# EuroESP32.net
KiCad netlist of a schematic drawn in EAGLE
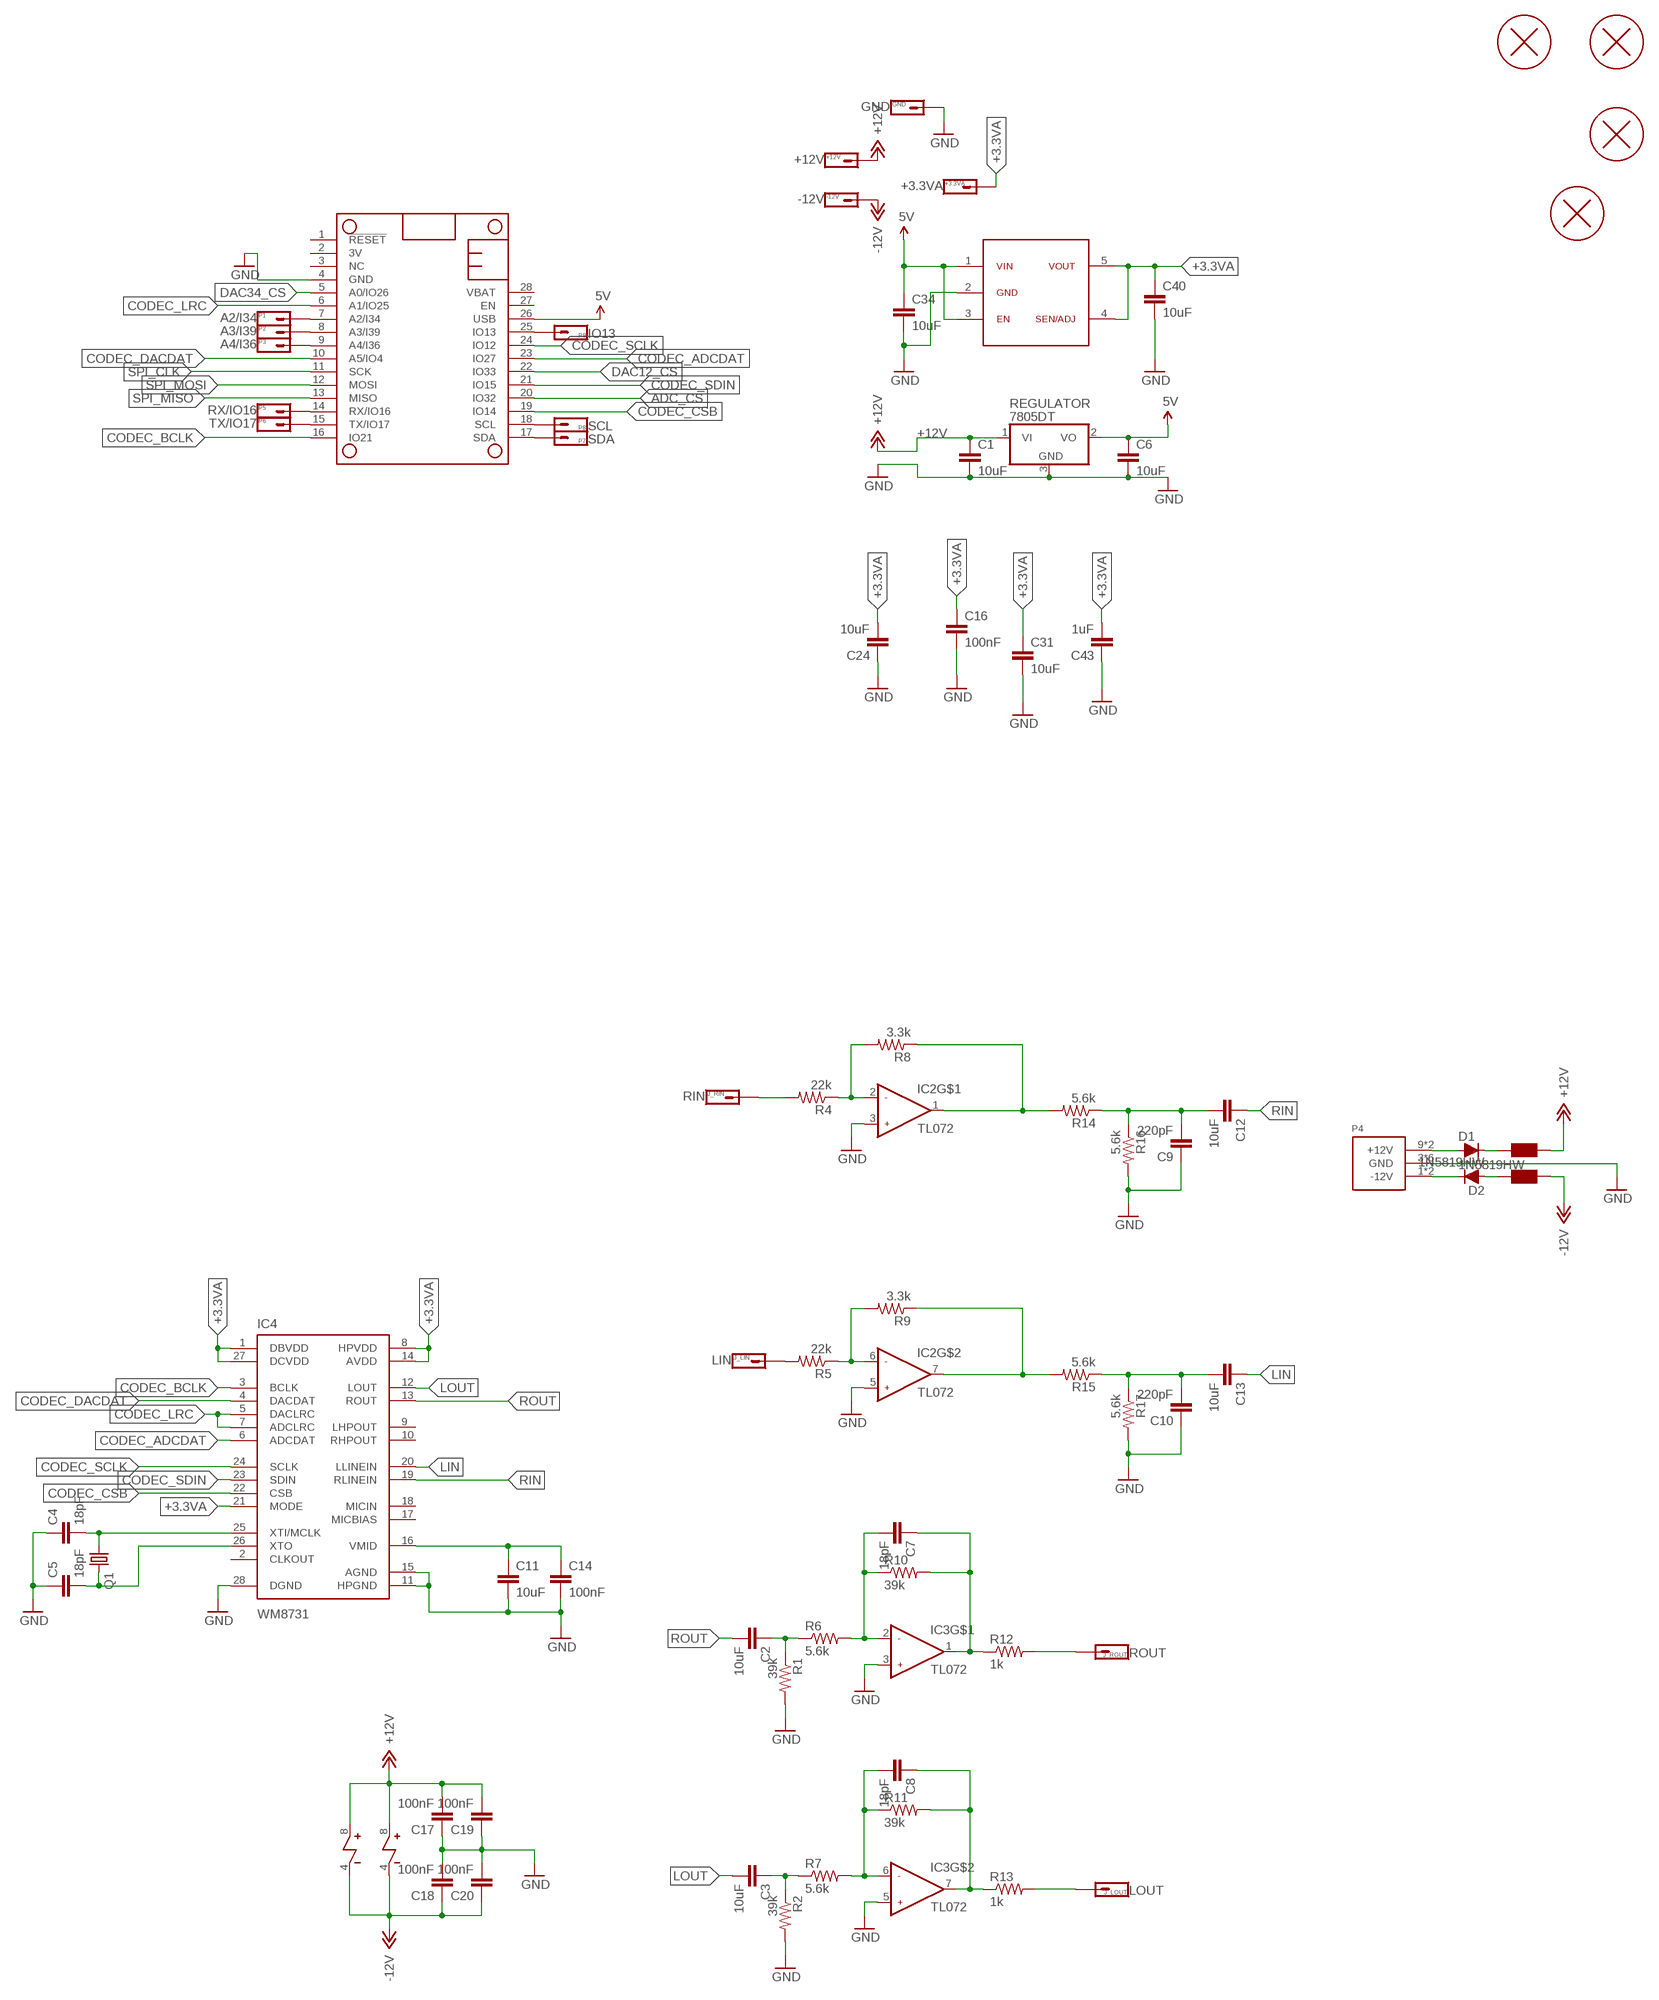
[diagram p0: schematic, sheet 1, part 1 of 2]
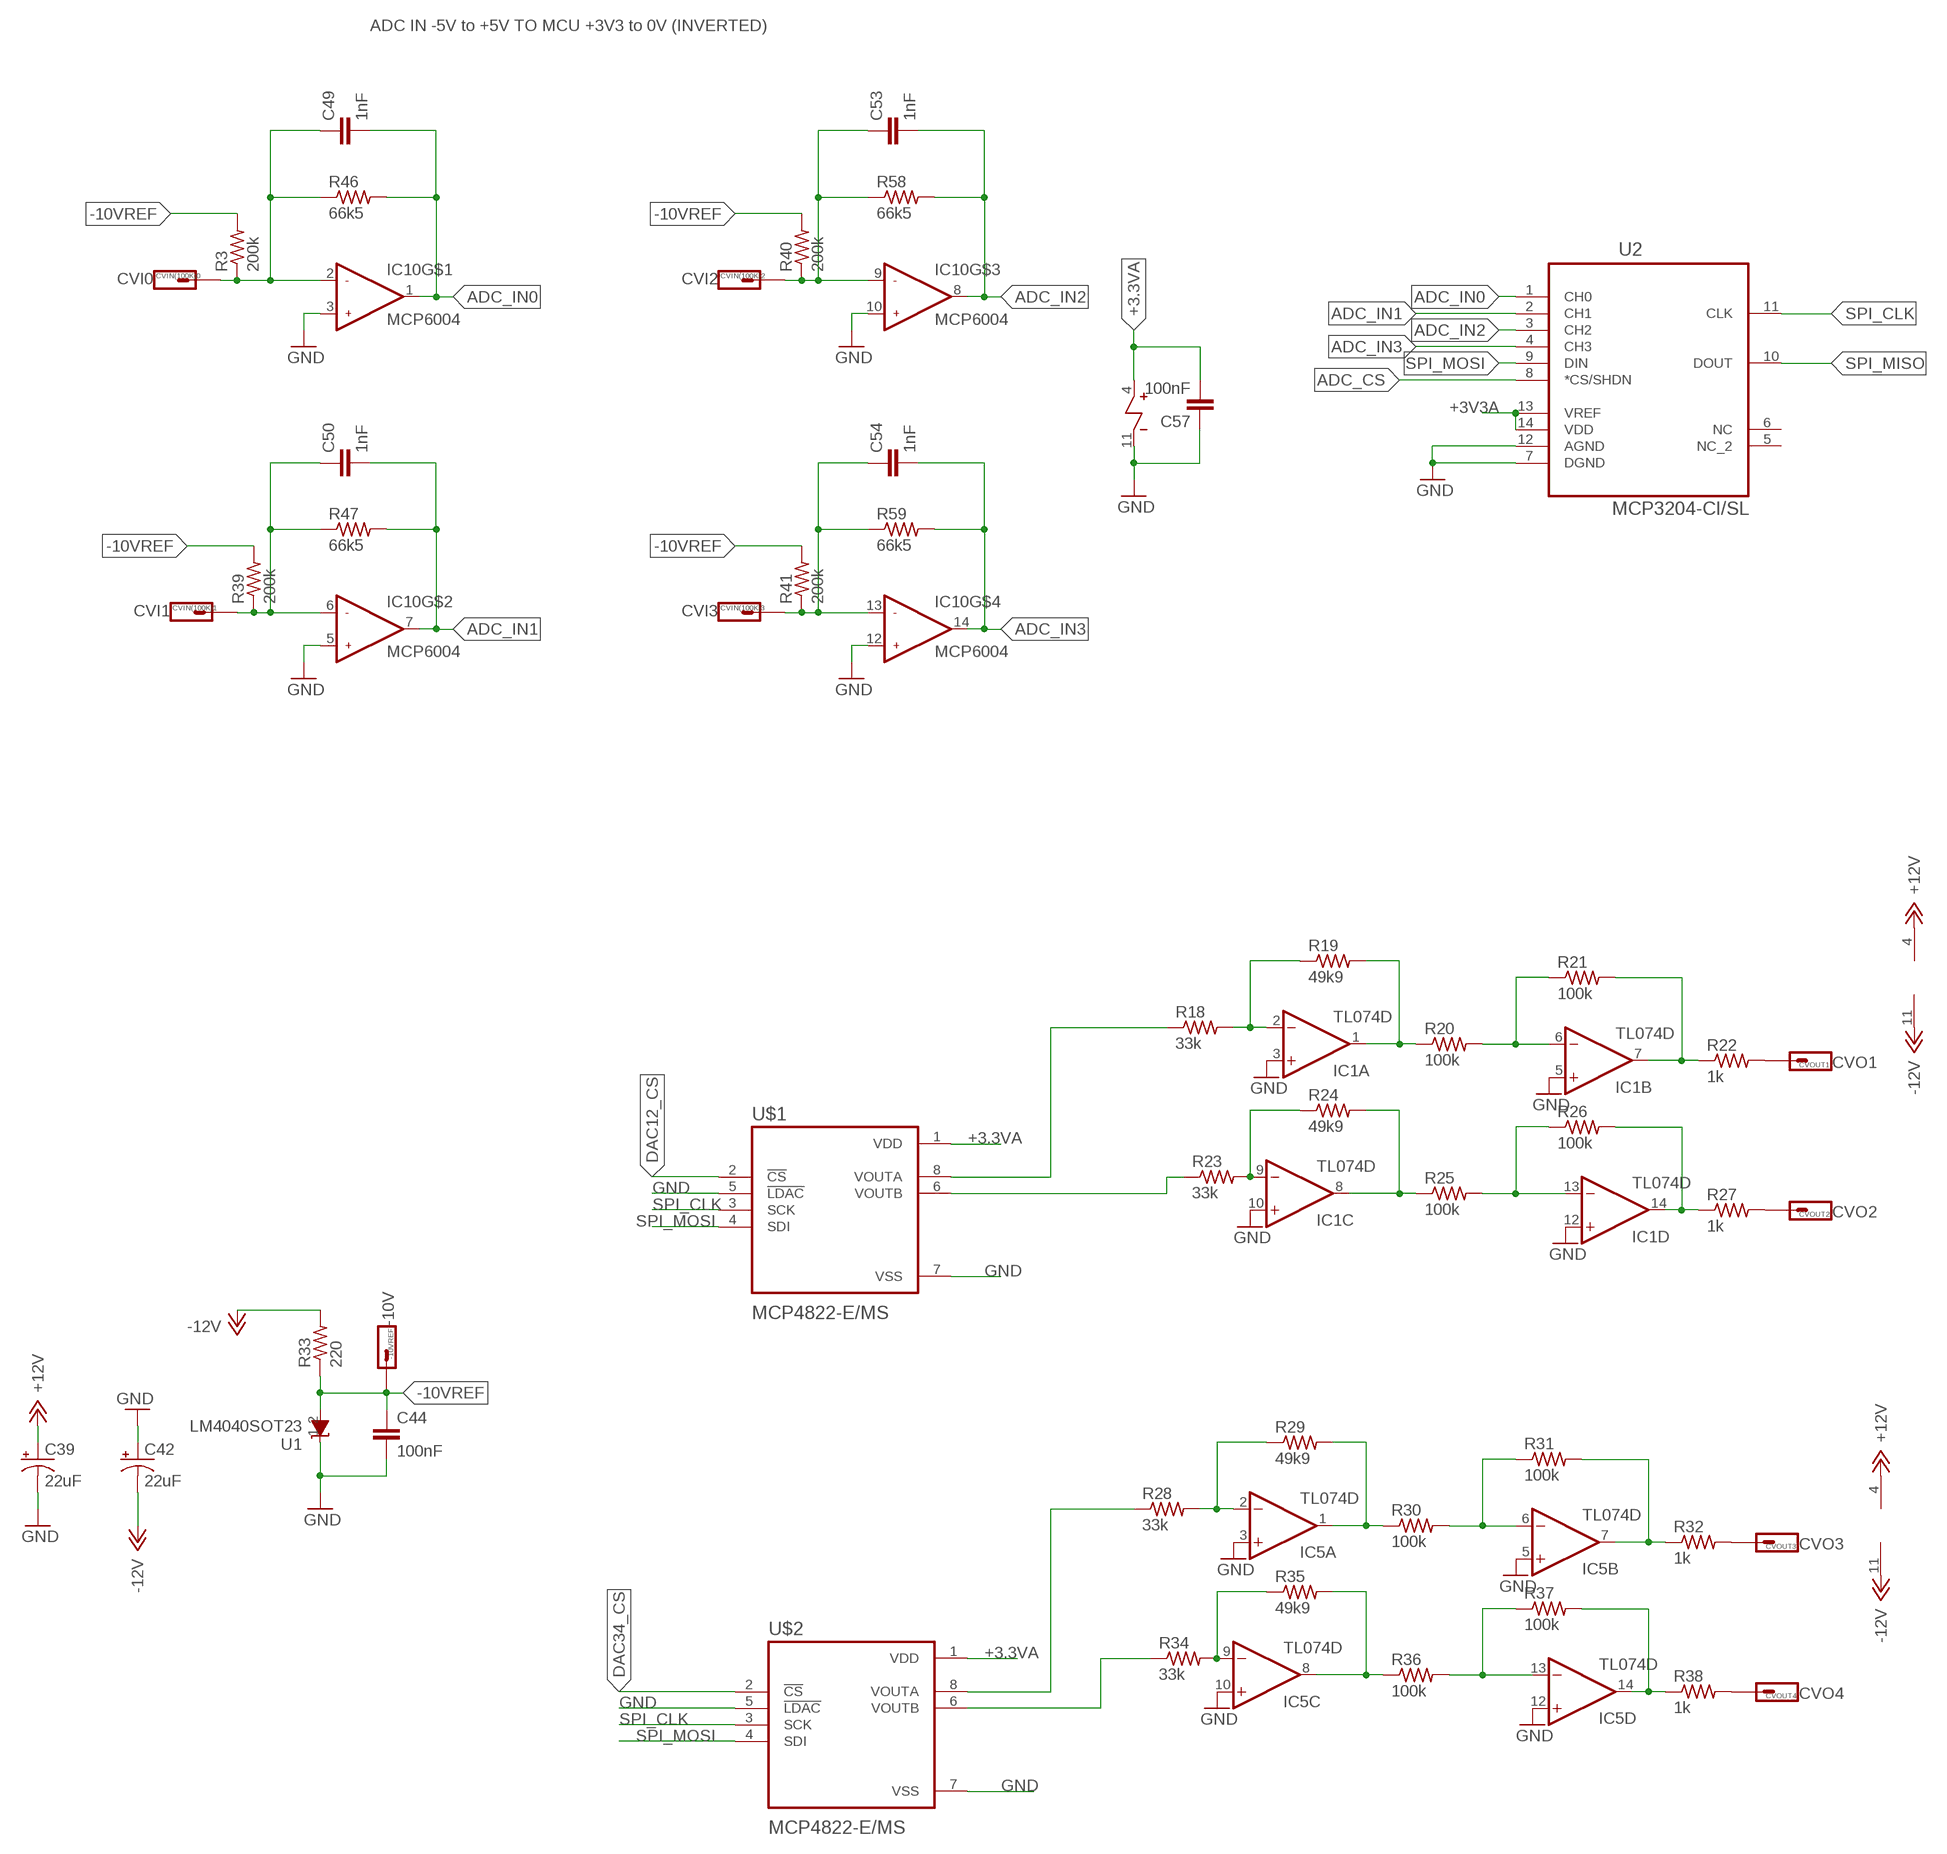
[diagram p1: schematic, sheet 1, part 2 of 2]

(export (version "E")
  (design (tool "Eeschema 10.0.6"))
  (components
    (comp (ref "+3.3VA")
      (value "+3.3VA")
      (footprint "eagle-import:1X01_SIDE_NAME")
      (libsource (lib "eagle-import") (part "HEADER-1X1"))
    )
    (comp (ref "+12V")
      (value "+12V")
      (footprint "eagle-import:1X01_SIDE_NAME")
      (libsource (lib "eagle-import") (part "HEADER-1X1"))
    )
    (comp (ref "-10VREF")
      (value "-10V")
      (footprint "eagle-import:1X01_SIDE_NAME")
      (libsource (lib "eagle-import") (part "HEADER-1X1"))
    )
    (comp (ref "-12V")
      (value "-12V")
      (footprint "eagle-import:1X01_SIDE_NAME")
      (libsource (lib "eagle-import") (part "HEADER-1X1"))
    )
    (comp (ref "C1")
      (value "10uF")
      (footprint "eagle-import:R1210")
      (libsource (lib "eagle-import") (part "CAPACITOR1210"))
    )
    (comp (ref "C2")
      (value "10uF")
      (footprint "eagle-import:R0805")
      (libsource (lib "eagle-import") (part "CAPACITOR0805"))
    )
    (comp (ref "C3")
      (value "10uF")
      (footprint "eagle-import:R0805")
      (libsource (lib "eagle-import") (part "CAPACITOR0805"))
    )
    (comp (ref "C4")
      (value "18pF")
      (footprint "eagle-import:RESISTOR_0603")
      (libsource (lib "eagle-import") (part "CAPACITOR"))
    )
    (comp (ref "C5")
      (value "18pF")
      (footprint "eagle-import:RESISTOR_0603")
      (libsource (lib "eagle-import") (part "CAPACITOR"))
    )
    (comp (ref "C6")
      (value "10uF")
      (footprint "eagle-import:R1210")
      (libsource (lib "eagle-import") (part "CAPACITOR1210"))
    )
    (comp (ref "C7")
      (value "18pF")
      (footprint "eagle-import:RESISTOR_0603")
      (libsource (lib "eagle-import") (part "CAPACITOR"))
    )
    (comp (ref "C8")
      (value "18pF")
      (footprint "eagle-import:RESISTOR_0603")
      (libsource (lib "eagle-import") (part "CAPACITOR"))
    )
    (comp (ref "C9")
      (value "220pF")
      (footprint "eagle-import:RESISTOR_0603")
      (libsource (lib "eagle-import") (part "CAPACITOR"))
    )
    (comp (ref "C10")
      (value "220pF")
      (footprint "eagle-import:RESISTOR_0603")
      (libsource (lib "eagle-import") (part "CAPACITOR"))
    )
    (comp (ref "C11")
      (value "10uF")
      (footprint "eagle-import:R0805")
      (libsource (lib "eagle-import") (part "CAPACITOR0805"))
    )
    (comp (ref "C12")
      (value "10uF")
      (footprint "eagle-import:R0805")
      (libsource (lib "eagle-import") (part "CAPACITOR0805"))
    )
    (comp (ref "C13")
      (value "10uF")
      (footprint "eagle-import:R0805")
      (libsource (lib "eagle-import") (part "CAPACITOR0805"))
    )
    (comp (ref "C14")
      (value "100nF")
      (footprint "eagle-import:RESISTOR_0603")
      (libsource (lib "eagle-import") (part "CAPACITOR"))
    )
    (comp (ref "C16")
      (value "100nF")
      (footprint "eagle-import:RESISTOR_0603")
      (libsource (lib "eagle-import") (part "CAPACITOR"))
    )
    (comp (ref "C17")
      (value "100nF")
      (footprint "eagle-import:RESISTOR_0603")
      (libsource (lib "eagle-import") (part "CAPACITOR"))
    )
    (comp (ref "C18")
      (value "100nF")
      (footprint "eagle-import:RESISTOR_0603")
      (libsource (lib "eagle-import") (part "CAPACITOR"))
    )
    (comp (ref "C19")
      (value "100nF")
      (footprint "eagle-import:RESISTOR_0603")
      (libsource (lib "eagle-import") (part "CAPACITOR"))
    )
    (comp (ref "C20")
      (value "100nF")
      (footprint "eagle-import:RESISTOR_0603")
      (libsource (lib "eagle-import") (part "CAPACITOR"))
    )
    (comp (ref "C24")
      (value "10uF")
      (footprint "eagle-import:R0805")
      (libsource (lib "eagle-import") (part "CAPACITOR0805"))
    )
    (comp (ref "C31")
      (value "10uF")
      (footprint "eagle-import:R0805")
      (libsource (lib "eagle-import") (part "CAPACITOR0805"))
    )
    (comp (ref "C34")
      (value "10uF")
      (footprint "eagle-import:R1210")
      (libsource (lib "eagle-import") (part "CAPACITOR1210"))
    )
    (comp (ref "C39")
      (value "22uF")
      (footprint "eagle-import:1206_POL")
      (libsource (lib "eagle-import") (part "CAP_POL1206_TANT"))
    )
    (comp (ref "C40")
      (value "10uF")
      (footprint "eagle-import:R0805")
      (libsource (lib "eagle-import") (part "CAPACITOR0805"))
    )
    (comp (ref "C42")
      (value "22uF")
      (footprint "eagle-import:1206_POL")
      (libsource (lib "eagle-import") (part "CAP_POL1206_TANT"))
    )
    (comp (ref "C43")
      (value "1uF")
      (footprint "eagle-import:RESISTOR_0603")
      (libsource (lib "eagle-import") (part "CAPACITOR"))
    )
    (comp (ref "C44")
      (value "100nF")
      (footprint "eagle-import:RESISTOR_0603")
      (libsource (lib "eagle-import") (part "CAPACITOR"))
    )
    (comp (ref "C49")
      (value "1nF")
      (footprint "eagle-import:RESISTOR_0603")
      (libsource (lib "eagle-import") (part "CAPACITOR"))
    )
    (comp (ref "C50")
      (value "1nF")
      (footprint "eagle-import:RESISTOR_0603")
      (libsource (lib "eagle-import") (part "CAPACITOR"))
    )
    (comp (ref "C53")
      (value "1nF")
      (footprint "eagle-import:RESISTOR_0603")
      (libsource (lib "eagle-import") (part "CAPACITOR"))
    )
    (comp (ref "C54")
      (value "1nF")
      (footprint "eagle-import:RESISTOR_0603")
      (libsource (lib "eagle-import") (part "CAPACITOR"))
    )
    (comp (ref "C57")
      (value "100nF")
      (footprint "eagle-import:RESISTOR_0603")
      (libsource (lib "eagle-import") (part "CAPACITOR"))
    )
    (comp (ref "CVIN(100K)0")
      (value "CVI0")
      (footprint "eagle-import:1X01_SIDE_NAME")
      (libsource (lib "eagle-import") (part "HEADER-1X1"))
    )
    (comp (ref "CVIN(100K)1")
      (value "CVI1")
      (footprint "eagle-import:1X01_SIDE_NAME")
      (libsource (lib "eagle-import") (part "HEADER-1X1"))
    )
    (comp (ref "CVIN(100K)2")
      (value "CVI2")
      (footprint "eagle-import:1X01_SIDE_NAME")
      (libsource (lib "eagle-import") (part "HEADER-1X1"))
    )
    (comp (ref "CVIN(100K)3")
      (value "CVI3")
      (footprint "eagle-import:1X01_SIDE_NAME")
      (libsource (lib "eagle-import") (part "HEADER-1X1"))
    )
    (comp (ref "CVOUT1")
      (value "CVO1")
      (footprint "eagle-import:1X01_SIDE_NAME")
      (libsource (lib "eagle-import") (part "HEADER-1X1"))
    )
    (comp (ref "CVOUT2")
      (value "CVO2")
      (footprint "eagle-import:1X01_SIDE_NAME")
      (libsource (lib "eagle-import") (part "HEADER-1X1"))
    )
    (comp (ref "CVOUT3")
      (value "CVO3")
      (footprint "eagle-import:1X01_SIDE_NAME")
      (libsource (lib "eagle-import") (part "HEADER-1X1"))
    )
    (comp (ref "CVOUT4")
      (value "CVO4")
      (footprint "eagle-import:1X01_SIDE_NAME")
      (libsource (lib "eagle-import") (part "HEADER-1X1"))
    )
    (comp (ref "D1")
      (value "1N5819HW")
      (footprint "eagle-import:SOD123")
      (libsource (lib "eagle-import") (part "DIODE"))
    )
    (comp (ref "D2")
      (value "1N5819HW")
      (footprint "eagle-import:SOD123")
      (libsource (lib "eagle-import") (part "DIODE"))
    )
    (comp (ref "F1")
      (value "Würth Electronics 742792664")
      (footprint "eagle-import:R0805")
      (libsource (lib "eagle-import") (part "FERRITE-BEAD0805"))
    )
    (comp (ref "F2")
      (value "Würth Electronics 742792664")
      (footprint "eagle-import:R0805")
      (libsource (lib "eagle-import") (part "FERRITE-BEAD0805"))
    )
    (comp (ref "GND")
      (value "GND")
      (footprint "eagle-import:1X01_SIDE_NAME")
      (libsource (lib "eagle-import") (part "HEADER-1X1"))
    )
    (comp (ref "H1")
      (value "PCB_SCREW")
      (footprint "eagle-import:PCB_SCREW")
      (libsource (lib "eagle-import") (part "PCB_SCREW"))
    )
    (comp (ref "H3")
      (value "PCB_SCREW")
      (footprint "eagle-import:PCB_SCREW")
      (libsource (lib "eagle-import") (part "PCB_SCREW"))
    )
    (comp (ref "H4")
      (value "PCB_SCREW")
      (footprint "eagle-import:PCB_SCREW")
      (libsource (lib "eagle-import") (part "PCB_SCREW"))
    )
    (comp (ref "H5")
      (value "PCB_SCREW")
      (footprint "eagle-import:PCB_SCREW")
      (libsource (lib "eagle-import") (part "PCB_SCREW"))
    )
    (comp (ref "IC1")
      (value "TL074D")
      (footprint "eagle-import:SO14")
      (libsource (lib "eagle-import") (part "TL074D"))
    )
    (comp (ref "IC2")
      (value "TL072")
      (footprint "eagle-import:SOIC8")
      (libsource (lib "eagle-import") (part "OPAMP_DUAL"))
    )
    (comp (ref "IC3")
      (value "TL072")
      (footprint "eagle-import:SOIC8")
      (libsource (lib "eagle-import") (part "OPAMP_DUAL"))
    )
    (comp (ref "IC4")
      (value "WM8731")
      (footprint "eagle-import:SSOP28")
      (libsource (lib "eagle-import") (part "WM8731"))
    )
    (comp (ref "IC5")
      (value "TL074D")
      (footprint "eagle-import:SO14")
      (libsource (lib "eagle-import") (part "TL074D"))
    )
    (comp (ref "IC7")
      (value "ADP7118")
      (footprint "eagle-import:SOT23-5L")
      (libsource (lib "eagle-import") (part "ADP7118"))
    )
    (comp (ref "IC10")
      (value "MCP6004")
      (footprint "eagle-import:TSSOP14")
      (libsource (lib "eagle-import") (part "OPAMP_QUADPWR"))
    )
    (comp (ref "J_LIN")
      (value "LIN")
      (footprint "eagle-import:1X01_SIDE_NAME")
      (libsource (lib "eagle-import") (part "HEADER-1X1"))
    )
    (comp (ref "J_LOUT")
      (value "LOUT")
      (footprint "eagle-import:1X01_SIDE_NAME")
      (libsource (lib "eagle-import") (part "HEADER-1X1"))
    )
    (comp (ref "J_RIN")
      (value "RIN")
      (footprint "eagle-import:1X01_SIDE_NAME")
      (libsource (lib "eagle-import") (part "HEADER-1X1"))
    )
    (comp (ref "J_ROUT")
      (value "ROUT")
      (footprint "eagle-import:1X01_SIDE_NAME")
      (libsource (lib "eagle-import") (part "HEADER-1X1"))
    )
    (comp (ref "MS2")
      (value "FEATHER_HUZZAH32NO_DRILL")
      (footprint "eagle-import:FEATHERWING_NODRILL")
      (libsource (lib "eagle-import") (part "FEATHER_HUZZAH32NO_DRILL"))
    )
    (comp (ref "P1")
      (value "A2/I34")
      (footprint "eagle-import:1X01_SIDE_NAME")
      (libsource (lib "eagle-import") (part "HEADER-1X1"))
    )
    (comp (ref "P2")
      (value "A3/I39")
      (footprint "eagle-import:1X01_SIDE_NAME")
      (libsource (lib "eagle-import") (part "HEADER-1X1"))
    )
    (comp (ref "P3")
      (value "A4/I36")
      (footprint "eagle-import:1X01_SIDE_NAME")
      (libsource (lib "eagle-import") (part "HEADER-1X1"))
    )
    (comp (ref "P4")
      (value "POWER_SIMPLE10")
      (footprint "eagle-import:POWER_10")
      (libsource (lib "eagle-import") (part "POWER_SIMPLE10"))
    )
    (comp (ref "P5")
      (value "RX/IO16")
      (footprint "eagle-import:1X01_SIDE_NAME")
      (libsource (lib "eagle-import") (part "HEADER-1X1"))
    )
    (comp (ref "P6")
      (value "TX/IO17")
      (footprint "eagle-import:1X01_SIDE_NAME")
      (libsource (lib "eagle-import") (part "HEADER-1X1"))
    )
    (comp (ref "P7")
      (value "SDA")
      (footprint "eagle-import:1X01_SIDE_NAME")
      (libsource (lib "eagle-import") (part "HEADER-1X1"))
    )
    (comp (ref "P8")
      (value "SCL")
      (footprint "eagle-import:1X01_SIDE_NAME")
      (libsource (lib "eagle-import") (part "HEADER-1X1"))
    )
    (comp (ref "P9")
      (value "IO13")
      (footprint "eagle-import:1X01_SIDE_NAME")
      (libsource (lib "eagle-import") (part "HEADER-1X1"))
    )
    (comp (ref "Q1")
      (value "CRYSTAL")
      (footprint "eagle-import:HC49UP")
      (libsource (lib "eagle-import") (part "CRYSTAL"))
    )
    (comp (ref "R1")
      (value "39k")
      (footprint "eagle-import:RESISTOR_0603")
      (libsource (lib "eagle-import") (part "RESISTOR"))
    )
    (comp (ref "R2")
      (value "39k")
      (footprint "eagle-import:RESISTOR_0603")
      (libsource (lib "eagle-import") (part "RESISTOR"))
    )
    (comp (ref "R3")
      (value "200k")
      (footprint "eagle-import:RESISTOR_0603")
      (libsource (lib "eagle-import") (part "RESISTOR"))
    )
    (comp (ref "R4")
      (value "22k")
      (footprint "eagle-import:RESISTOR_0603")
      (libsource (lib "eagle-import") (part "RESISTOR"))
    )
    (comp (ref "R5")
      (value "22k")
      (footprint "eagle-import:RESISTOR_0603")
      (libsource (lib "eagle-import") (part "RESISTOR"))
    )
    (comp (ref "R6")
      (value "5.6k")
      (footprint "eagle-import:RESISTOR_0603")
      (libsource (lib "eagle-import") (part "RESISTOR"))
    )
    (comp (ref "R7")
      (value "5.6k")
      (footprint "eagle-import:RESISTOR_0603")
      (libsource (lib "eagle-import") (part "RESISTOR"))
    )
    (comp (ref "R8")
      (value "3.3k")
      (footprint "eagle-import:RESISTOR_0603")
      (libsource (lib "eagle-import") (part "RESISTOR"))
    )
    (comp (ref "R9")
      (value "3.3k")
      (footprint "eagle-import:RESISTOR_0603")
      (libsource (lib "eagle-import") (part "RESISTOR"))
    )
    (comp (ref "R10")
      (value "39k")
      (footprint "eagle-import:RESISTOR_0603")
      (libsource (lib "eagle-import") (part "RESISTOR"))
    )
    (comp (ref "R11")
      (value "39k")
      (footprint "eagle-import:RESISTOR_0603")
      (libsource (lib "eagle-import") (part "RESISTOR"))
    )
    (comp (ref "R12")
      (value "1k")
      (footprint "eagle-import:RESISTOR_0603")
      (libsource (lib "eagle-import") (part "RESISTOR"))
    )
    (comp (ref "R13")
      (value "1k")
      (footprint "eagle-import:RESISTOR_0603")
      (libsource (lib "eagle-import") (part "RESISTOR"))
    )
    (comp (ref "R14")
      (value "5.6k")
      (footprint "eagle-import:RESISTOR_0603")
      (libsource (lib "eagle-import") (part "RESISTOR"))
    )
    (comp (ref "R15")
      (value "5.6k")
      (footprint "eagle-import:RESISTOR_0603")
      (libsource (lib "eagle-import") (part "RESISTOR"))
    )
    (comp (ref "R16")
      (value "5.6k")
      (footprint "eagle-import:RESISTOR_0603")
      (libsource (lib "eagle-import") (part "RESISTOR"))
    )
    (comp (ref "R17")
      (value "5.6k")
      (footprint "eagle-import:RESISTOR_0603")
      (libsource (lib "eagle-import") (part "RESISTOR"))
    )
    (comp (ref "R18")
      (value "33k")
      (footprint "eagle-import:RESISTOR_0603")
      (libsource (lib "eagle-import") (part "RESISTOR"))
    )
    (comp (ref "R19")
      (value "49k9")
      (footprint "eagle-import:RESISTOR_0603")
      (libsource (lib "eagle-import") (part "RESISTOR"))
    )
    (comp (ref "R20")
      (value "100k")
      (footprint "eagle-import:RESISTOR_0603")
      (libsource (lib "eagle-import") (part "RESISTOR"))
    )
    (comp (ref "R21")
      (value "100k")
      (footprint "eagle-import:RESISTOR_0603")
      (libsource (lib "eagle-import") (part "RESISTOR"))
    )
    (comp (ref "R22")
      (value "1k")
      (footprint "eagle-import:RESISTOR_0603")
      (libsource (lib "eagle-import") (part "RESISTOR"))
    )
    (comp (ref "R23")
      (value "33k")
      (footprint "eagle-import:RESISTOR_0603")
      (libsource (lib "eagle-import") (part "RESISTOR"))
    )
    (comp (ref "R24")
      (value "49k9")
      (footprint "eagle-import:RESISTOR_0603")
      (libsource (lib "eagle-import") (part "RESISTOR"))
    )
    (comp (ref "R25")
      (value "100k")
      (footprint "eagle-import:RESISTOR_0603")
      (libsource (lib "eagle-import") (part "RESISTOR"))
    )
    (comp (ref "R26")
      (value "100k")
      (footprint "eagle-import:RESISTOR_0603")
      (libsource (lib "eagle-import") (part "RESISTOR"))
    )
    (comp (ref "R27")
      (value "1k")
      (footprint "eagle-import:RESISTOR_0603")
      (libsource (lib "eagle-import") (part "RESISTOR"))
    )
    (comp (ref "R28")
      (value "33k")
      (footprint "eagle-import:RESISTOR_0603")
      (libsource (lib "eagle-import") (part "RESISTOR"))
    )
    (comp (ref "R29")
      (value "49k9")
      (footprint "eagle-import:RESISTOR_0603")
      (libsource (lib "eagle-import") (part "RESISTOR"))
    )
    (comp (ref "R30")
      (value "100k")
      (footprint "eagle-import:RESISTOR_0603")
      (libsource (lib "eagle-import") (part "RESISTOR"))
    )
    (comp (ref "R31")
      (value "100k")
      (footprint "eagle-import:RESISTOR_0603")
      (libsource (lib "eagle-import") (part "RESISTOR"))
    )
    (comp (ref "R32")
      (value "1k")
      (footprint "eagle-import:RESISTOR_0603")
      (libsource (lib "eagle-import") (part "RESISTOR"))
    )
    (comp (ref "R33")
      (value "220")
      (footprint "eagle-import:RESISTOR_0603")
      (libsource (lib "eagle-import") (part "RESISTOR"))
    )
    (comp (ref "R34")
      (value "33k")
      (footprint "eagle-import:RESISTOR_0603")
      (libsource (lib "eagle-import") (part "RESISTOR"))
    )
    (comp (ref "R35")
      (value "49k9")
      (footprint "eagle-import:RESISTOR_0603")
      (libsource (lib "eagle-import") (part "RESISTOR"))
    )
    (comp (ref "R36")
      (value "100k")
      (footprint "eagle-import:RESISTOR_0603")
      (libsource (lib "eagle-import") (part "RESISTOR"))
    )
    (comp (ref "R37")
      (value "100k")
      (footprint "eagle-import:RESISTOR_0603")
      (libsource (lib "eagle-import") (part "RESISTOR"))
    )
    (comp (ref "R38")
      (value "1k")
      (footprint "eagle-import:RESISTOR_0603")
      (libsource (lib "eagle-import") (part "RESISTOR"))
    )
    (comp (ref "R39")
      (value "200k")
      (footprint "eagle-import:RESISTOR_0603")
      (libsource (lib "eagle-import") (part "RESISTOR"))
    )
    (comp (ref "R40")
      (value "200k")
      (footprint "eagle-import:RESISTOR_0603")
      (libsource (lib "eagle-import") (part "RESISTOR"))
    )
    (comp (ref "R41")
      (value "200k")
      (footprint "eagle-import:RESISTOR_0603")
      (libsource (lib "eagle-import") (part "RESISTOR"))
    )
    (comp (ref "R46")
      (value "66k5")
      (footprint "eagle-import:RESISTOR_0603")
      (libsource (lib "eagle-import") (part "RESISTOR"))
    )
    (comp (ref "R47")
      (value "66k5")
      (footprint "eagle-import:RESISTOR_0603")
      (libsource (lib "eagle-import") (part "RESISTOR"))
    )
    (comp (ref "R58")
      (value "66k5")
      (footprint "eagle-import:RESISTOR_0603")
      (libsource (lib "eagle-import") (part "RESISTOR"))
    )
    (comp (ref "R59")
      (value "66k5")
      (footprint "eagle-import:RESISTOR_0603")
      (libsource (lib "eagle-import") (part "RESISTOR"))
    )
    (comp (ref "REGULATOR")
      (value "7805DT")
      (footprint "eagle-import:TO252")
      (libsource (lib "eagle-import") (part "78DT05"))
    )
    (comp (ref "U$1")
      (value "MCP4822-E/MS")
      (footprint "eagle-import:SOP65P490X110-8N")
      (fields (field (name "MF") "Microchip Technology"))
      (libsource (lib "eagle-import") (part "MCP4822-E/MS"))
    )
    (comp (ref "U$2")
      (value "MCP4822-E/MS")
      (footprint "eagle-import:SOP65P490X110-8N")
      (fields (field (name "MF") "Microchip Technology"))
      (libsource (lib "eagle-import") (part "MCP4822-E/MS"))
    )
    (comp (ref "U1")
      (value "LM4040SOT23")
      (footprint "eagle-import:SOT23")
      (libsource (lib "eagle-import") (part "LM4040SOT23"))
    )
    (comp (ref "U2")
      (value "MCP3204-CI/SL")
      (footprint "eagle-import:SOIC127P600X175-14N")
      (libsource (lib "eagle-import") (part "MCP3204-CI/SL"))
    )
  )
  (nets
    (net (code "1") (name "+3.3VA") (class "Default")
      (node (ref "+3.3VA") (pin "1") (pinfunction "1_1") (pintype "passive"))
      (node (ref "C16") (pin "1") (pinfunction "1_1") (pintype "passive"))
      (node (ref "C24") (pin "2") (pinfunction "2_2") (pintype "passive"))
      (node (ref "C31") (pin "1") (pinfunction "1_1") (pintype "passive"))
      (node (ref "C40") (pin "1") (pinfunction "1_1") (pintype "passive"))
      (node (ref "C43") (pin "2") (pinfunction "2_2") (pintype "passive"))
      (node (ref "C57") (pin "2") (pinfunction "2_2") (pintype "passive"))
      (node (ref "IC10") (pin "4") (pinfunction "P$1_4") (pintype "bidirectional"))
      (node (ref "IC4") (pin "1") (pinfunction "DBVDD_1") (pintype "bidirectional"))
      (node (ref "IC4") (pin "14") (pinfunction "AVDD_14") (pintype "bidirectional"))
      (node (ref "IC4") (pin "21") (pinfunction "MODE_21") (pintype "bidirectional"))
      (node (ref "IC4") (pin "27") (pinfunction "DCVDD_27") (pintype "bidirectional"))
      (node (ref "IC4") (pin "8") (pinfunction "HPVDD_8") (pintype "bidirectional"))
      (node (ref "IC7") (pin "4") (pinfunction "P$4_4") (pintype "bidirectional"))
      (node (ref "IC7") (pin "5") (pinfunction "P$5_5") (pintype "bidirectional"))
      (node (ref "U$1") (pin "1") (pinfunction "VDD_1") (pintype "power_in"))
      (node (ref "U$2") (pin "1") (pinfunction "VDD_1") (pintype "power_in"))
    )
    (net (code "2") (name "+12V") (class "Default")
      (node (ref "+12V") (pin "1") (pinfunction "1_1") (pintype "passive"))
      (node (ref "C1") (pin "1") (pinfunction "1_1") (pintype "passive"))
      (node (ref "C17") (pin "2") (pinfunction "2_2") (pintype "passive"))
      (node (ref "C19") (pin "2") (pinfunction "2_2") (pintype "passive"))
      (node (ref "C39") (pin "2") (pinfunction "+_2") (pintype "passive"))
      (node (ref "F1") (pin "1") (pinfunction "P$1_1") (pintype "bidirectional"))
      (node (ref "IC1") (pin "4") (pinfunction "V+_4") (pintype "power_in"))
      (node (ref "IC2") (pin "8") (pinfunction "P$1_8") (pintype "bidirectional"))
      (node (ref "IC3") (pin "8") (pinfunction "P$1_8") (pintype "bidirectional"))
      (node (ref "IC5") (pin "4") (pinfunction "V+_4") (pintype "power_in"))
      (node (ref "REGULATOR") (pin "1") (pinfunction "VI_1") (pintype "input"))
    )
    (net (code "3") (name "-10VREF") (class "Default")
      (node (ref "-10VREF") (pin "1") (pinfunction "1_1") (pintype "passive"))
      (node (ref "C44") (pin "1") (pinfunction "1_1") (pintype "passive"))
      (node (ref "R3") (pin "2") (pinfunction "2_2") (pintype "passive"))
      (node (ref "R33") (pin "1") (pinfunction "1_1") (pintype "passive"))
      (node (ref "R39") (pin "2") (pinfunction "2_2") (pintype "passive"))
      (node (ref "R40") (pin "2") (pinfunction "2_2") (pintype "passive"))
      (node (ref "R41") (pin "2") (pinfunction "2_2") (pintype "passive"))
      (node (ref "U1") (pin "2") (pinfunction "A_2") (pintype "passive"))
    )
    (net (code "4") (name "-12V") (class "Default")
      (node (ref "-12V") (pin "1") (pinfunction "1_1") (pintype "passive"))
      (node (ref "C18") (pin "1") (pinfunction "1_1") (pintype "passive"))
      (node (ref "C20") (pin "1") (pinfunction "1_1") (pintype "passive"))
      (node (ref "C42") (pin "1") (pinfunction "-_1") (pintype "passive"))
      (node (ref "F2") (pin "1") (pinfunction "P$1_1") (pintype "bidirectional"))
      (node (ref "IC1") (pin "11") (pinfunction "V-_11") (pintype "power_in"))
      (node (ref "IC2") (pin "4") (pinfunction "P$2_4") (pintype "bidirectional"))
      (node (ref "IC3") (pin "4") (pinfunction "P$2_4") (pintype "bidirectional"))
      (node (ref "IC5") (pin "11") (pinfunction "V-_11") (pintype "power_in"))
      (node (ref "R33") (pin "2") (pinfunction "2_2") (pintype "passive"))
    )
    (net (code "5") (name "/+3V3A") (class "Default")
      (node (ref "U2") (pin "13") (pinfunction "VREF_13") (pintype "input"))
      (node (ref "U2") (pin "14") (pinfunction "VDD_14") (pintype "power_in"))
    )
    (net (code "6") (name "/3V") (class "Default")
      (node (ref "MS2") (pin "2") (pinfunction "3V_2") (pintype "power_in"))
    )
    (net (code "7") (name "/VBAT") (class "Default")
      (node (ref "MS2") (pin "28") (pinfunction "VBAT_28") (pintype "power_in"))
    )
    (net (code "8") (name "5V") (class "Default")
      (node (ref "C34") (pin "1") (pinfunction "1_1") (pintype "passive"))
      (node (ref "C6") (pin "1") (pinfunction "1_1") (pintype "passive"))
      (node (ref "IC7") (pin "1") (pinfunction "P$1_1") (pintype "bidirectional"))
      (node (ref "IC7") (pin "3") (pinfunction "P$3_3") (pintype "bidirectional"))
      (node (ref "MS2") (pin "26") (pinfunction "USB_26") (pintype "power_in"))
      (node (ref "REGULATOR") (pin "2") (pinfunction "VO_2") (pintype "passive"))
    )
    (net (code "9") (name "ADC_CS") (class "Default")
      (node (ref "MS2") (pin "20") (pinfunction "IO32_20") (pintype "bidirectional"))
      (node (ref "U2") (pin "8") (pinfunction "*CS/SHDN_8") (pintype "input"))
    )
    (net (code "10") (name "ADC_IN0") (class "Default")
      (node (ref "C49") (pin "2") (pinfunction "2_2") (pintype "passive"))
      (node (ref "IC10") (pin "1") (pinfunction "P$3_1") (pintype "bidirectional"))
      (node (ref "R46") (pin "2") (pinfunction "2_2") (pintype "passive"))
      (node (ref "U2") (pin "1") (pinfunction "CH0_1") (pintype "input"))
    )
    (net (code "11") (name "ADC_IN1") (class "Default")
      (node (ref "C50") (pin "2") (pinfunction "2_2") (pintype "passive"))
      (node (ref "IC10") (pin "7") (pinfunction "P$3_7") (pintype "bidirectional"))
      (node (ref "R47") (pin "2") (pinfunction "2_2") (pintype "passive"))
      (node (ref "U2") (pin "2") (pinfunction "CH1_2") (pintype "input"))
    )
    (net (code "12") (name "ADC_IN2") (class "Default")
      (node (ref "C53") (pin "2") (pinfunction "2_2") (pintype "passive"))
      (node (ref "IC10") (pin "8") (pinfunction "P$3_8") (pintype "bidirectional"))
      (node (ref "R58") (pin "2") (pinfunction "2_2") (pintype "passive"))
      (node (ref "U2") (pin "3") (pinfunction "CH2_3") (pintype "input"))
    )
    (net (code "13") (name "ADC_IN3") (class "Default")
      (node (ref "C54") (pin "2") (pinfunction "2_2") (pintype "passive"))
      (node (ref "IC10") (pin "14") (pinfunction "P$3_14") (pintype "bidirectional"))
      (node (ref "R59") (pin "2") (pinfunction "2_2") (pintype "passive"))
      (node (ref "U2") (pin "4") (pinfunction "CH3_4") (pintype "input"))
    )
    (net (code "14") (name "CODEC_ADCDAT") (class "Default")
      (node (ref "IC4") (pin "6") (pinfunction "ADCDAT_6") (pintype "bidirectional"))
      (node (ref "MS2") (pin "23") (pinfunction "IO27_23") (pintype "bidirectional"))
    )
    (net (code "15") (name "CODEC_BCLK") (class "Default")
      (node (ref "IC4") (pin "3") (pinfunction "BCLK_3") (pintype "bidirectional"))
      (node (ref "MS2") (pin "16") (pinfunction "IO21_16") (pintype "passive"))
    )
    (net (code "16") (name "CODEC_CSB") (class "Default")
      (node (ref "IC4") (pin "22") (pinfunction "CSB_22") (pintype "bidirectional"))
      (node (ref "MS2") (pin "19") (pinfunction "IO14_19") (pintype "bidirectional"))
    )
    (net (code "17") (name "CODEC_DACDAT") (class "Default")
      (node (ref "IC4") (pin "4") (pinfunction "DACDAT_4") (pintype "bidirectional"))
      (node (ref "MS2") (pin "10") (pinfunction "A5/IO4_10") (pintype "bidirectional"))
    )
    (net (code "18") (name "CODEC_LRC") (class "Default")
      (node (ref "IC4") (pin "5") (pinfunction "DACLRC_5") (pintype "bidirectional"))
      (node (ref "IC4") (pin "7") (pinfunction "ADCLRC_7") (pintype "bidirectional"))
      (node (ref "MS2") (pin "6") (pinfunction "A1/IO25_6") (pintype "bidirectional"))
    )
    (net (code "19") (name "CODEC_SCLK") (class "Default")
      (node (ref "IC4") (pin "24") (pinfunction "SCLK_24") (pintype "bidirectional"))
      (node (ref "MS2") (pin "24") (pinfunction "IO12_24") (pintype "bidirectional"))
    )
    (net (code "20") (name "CODEC_SDIN") (class "Default")
      (node (ref "IC4") (pin "23") (pinfunction "SDIN_23") (pintype "bidirectional"))
      (node (ref "MS2") (pin "21") (pinfunction "IO15_21") (pintype "bidirectional"))
    )
    (net (code "21") (name "DAC12_CS") (class "Default")
      (node (ref "MS2") (pin "22") (pinfunction "IO33_22") (pintype "bidirectional"))
      (node (ref "U$1") (pin "2") (pinfunction "~{CS}_2") (pintype "input"))
    )
    (net (code "22") (name "DAC34_CS") (class "Default")
      (node (ref "MS2") (pin "5") (pinfunction "A0/IO26_5") (pintype "bidirectional"))
      (node (ref "U$2") (pin "2") (pinfunction "~{CS}_2") (pintype "input"))
    )
    (net (code "23") (name "GND") (class "Default")
      (node (ref "C1") (pin "2") (pinfunction "2_2") (pintype "passive"))
      (node (ref "C10") (pin "1") (pinfunction "1_1") (pintype "passive"))
      (node (ref "C11") (pin "2") (pinfunction "2_2") (pintype "passive"))
      (node (ref "C14") (pin "2") (pinfunction "2_2") (pintype "passive"))
      (node (ref "C16") (pin "2") (pinfunction "2_2") (pintype "passive"))
      (node (ref "C17") (pin "1") (pinfunction "1_1") (pintype "passive"))
      (node (ref "C18") (pin "2") (pinfunction "2_2") (pintype "passive"))
      (node (ref "C19") (pin "1") (pinfunction "1_1") (pintype "passive"))
      (node (ref "C20") (pin "2") (pinfunction "2_2") (pintype "passive"))
      (node (ref "C24") (pin "1") (pinfunction "1_1") (pintype "passive"))
      (node (ref "C31") (pin "2") (pinfunction "2_2") (pintype "passive"))
      (node (ref "C34") (pin "2") (pinfunction "2_2") (pintype "passive"))
      (node (ref "C39") (pin "1") (pinfunction "-_1") (pintype "passive"))
      (node (ref "C4") (pin "1") (pinfunction "1_1") (pintype "passive"))
      (node (ref "C40") (pin "2") (pinfunction "2_2") (pintype "passive"))
      (node (ref "C42") (pin "2") (pinfunction "+_2") (pintype "passive"))
      (node (ref "C43") (pin "1") (pinfunction "1_1") (pintype "passive"))
      (node (ref "C44") (pin "2") (pinfunction "2_2") (pintype "passive"))
      (node (ref "C5") (pin "1") (pinfunction "1_1") (pintype "passive"))
      (node (ref "C57") (pin "1") (pinfunction "1_1") (pintype "passive"))
      (node (ref "C6") (pin "2") (pinfunction "2_2") (pintype "passive"))
      (node (ref "C9") (pin "1") (pinfunction "1_1") (pintype "passive"))
      (node (ref "GND") (pin "1") (pinfunction "1_1") (pintype "passive"))
      (node (ref "IC1") (pin "10") (pinfunction "+IN_10") (pintype "input"))
      (node (ref "IC1") (pin "12") (pinfunction "+IN_12") (pintype "input"))
      (node (ref "IC1") (pin "3") (pinfunction "+IN_3") (pintype "input"))
      (node (ref "IC1") (pin "5") (pinfunction "+IN_5") (pintype "input"))
      (node (ref "IC10") (pin "10") (pinfunction "P$1_10") (pintype "bidirectional"))
      (node (ref "IC10") (pin "11") (pinfunction "P$2_11") (pintype "bidirectional"))
      (node (ref "IC10") (pin "12") (pinfunction "P$1_12") (pintype "bidirectional"))
      (node (ref "IC10") (pin "3") (pinfunction "P$1_3") (pintype "bidirectional"))
      (node (ref "IC10") (pin "5") (pinfunction "P$1_5") (pintype "bidirectional"))
      (node (ref "IC2") (pin "3") (pinfunction "P$1_3") (pintype "bidirectional"))
      (node (ref "IC2") (pin "5") (pinfunction "P$1_5") (pintype "bidirectional"))
      (node (ref "IC3") (pin "3") (pinfunction "P$1_3") (pintype "bidirectional"))
      (node (ref "IC3") (pin "5") (pinfunction "P$1_5") (pintype "bidirectional"))
      (node (ref "IC4") (pin "11") (pinfunction "HPGND_11") (pintype "bidirectional"))
      (node (ref "IC4") (pin "15") (pinfunction "AGND_15") (pintype "bidirectional"))
      (node (ref "IC4") (pin "28") (pinfunction "DGND_28") (pintype "bidirectional"))
      (node (ref "IC5") (pin "10") (pinfunction "+IN_10") (pintype "input"))
      (node (ref "IC5") (pin "12") (pinfunction "+IN_12") (pintype "input"))
      (node (ref "IC5") (pin "3") (pinfunction "+IN_3") (pintype "input"))
      (node (ref "IC5") (pin "5") (pinfunction "+IN_5") (pintype "input"))
      (node (ref "IC7") (pin "2") (pinfunction "P$2_2") (pintype "bidirectional"))
      (node (ref "MS2") (pin "4") (pinfunction "GND_4") (pintype "power_in"))
      (node (ref "P4") (pin "3") (pinfunction "GND_3") (pintype "bidirectional"))
      (node (ref "P4") (pin "4") (pinfunction "GND_4") (pintype "bidirectional"))
      (node (ref "P4") (pin "5") (pinfunction "GND_5") (pintype "bidirectional"))
      (node (ref "P4") (pin "6") (pinfunction "GND_6") (pintype "bidirectional"))
      (node (ref "P4") (pin "7") (pinfunction "GND_7") (pintype "bidirectional"))
      (node (ref "P4") (pin "8") (pinfunction "GND_8") (pintype "bidirectional"))
      (node (ref "R1") (pin "2") (pinfunction "2_2") (pintype "passive"))
      (node (ref "R16") (pin "2") (pinfunction "2_2") (pintype "passive"))
      (node (ref "R17") (pin "2") (pinfunction "2_2") (pintype "passive"))
      (node (ref "R2") (pin "2") (pinfunction "2_2") (pintype "passive"))
      (node (ref "REGULATOR") (pin "3") (pinfunction "GND_3") (pintype "passive"))
      (node (ref "U$1") (pin "5") (pinfunction "~{LDAC}_5") (pintype "input"))
      (node (ref "U$1") (pin "7") (pinfunction "VSS_7") (pintype "power_in"))
      (node (ref "U$2") (pin "5") (pinfunction "~{LDAC}_5") (pintype "input"))
      (node (ref "U$2") (pin "7") (pinfunction "VSS_7") (pintype "power_in"))
      (node (ref "U1") (pin "1") (pinfunction "C_1") (pintype "passive"))
      (node (ref "U2") (pin "12") (pinfunction "AGND_12") (pintype "passive"))
      (node (ref "U2") (pin "7") (pinfunction "DGND_7") (pintype "passive"))
    )
    (net (code "24") (name "LIN") (class "Default")
      (node (ref "C13") (pin "1") (pinfunction "1_1") (pintype "passive"))
      (node (ref "IC4") (pin "20") (pinfunction "LLINEIN_20") (pintype "bidirectional"))
    )
    (net (code "25") (name "LOUT") (class "Default")
      (node (ref "C3") (pin "2") (pinfunction "2_2") (pintype "passive"))
      (node (ref "IC4") (pin "12") (pinfunction "LOUT_12") (pintype "bidirectional"))
    )
    (net (code "26") (name "Net-(C2-Pad1)") (class "Default")
      (node (ref "C2") (pin "1") (pinfunction "1_1") (pintype "passive"))
      (node (ref "R1") (pin "1") (pinfunction "1_1") (pintype "passive"))
      (node (ref "R6") (pin "1") (pinfunction "1_1") (pintype "passive"))
    )
    (net (code "27") (name "Net-(C3-Pad1)") (class "Default")
      (node (ref "C3") (pin "1") (pinfunction "1_1") (pintype "passive"))
      (node (ref "R2") (pin "1") (pinfunction "1_1") (pintype "passive"))
      (node (ref "R7") (pin "1") (pinfunction "1_1") (pintype "passive"))
    )
    (net (code "28") (name "Net-(C10-Pad2)") (class "Default")
      (node (ref "C10") (pin "2") (pinfunction "2_2") (pintype "passive"))
      (node (ref "C13") (pin "2") (pinfunction "2_2") (pintype "passive"))
      (node (ref "R15") (pin "1") (pinfunction "1_1") (pintype "passive"))
      (node (ref "R17") (pin "1") (pinfunction "1_1") (pintype "passive"))
    )
    (net (code "29") (name "Net-(C12-Pad2)") (class "Default")
      (node (ref "C12") (pin "2") (pinfunction "2_2") (pintype "passive"))
      (node (ref "C9") (pin "2") (pinfunction "2_2") (pintype "passive"))
      (node (ref "R14") (pin "1") (pinfunction "1_1") (pintype "passive"))
      (node (ref "R16") (pin "1") (pinfunction "1_1") (pintype "passive"))
    )
    (net (code "30") (name "Net-(CVOUT1-Pad1)") (class "Default")
      (node (ref "CVOUT1") (pin "1") (pinfunction "1_1") (pintype "passive"))
      (node (ref "R22") (pin "2") (pinfunction "2_2") (pintype "passive"))
    )
    (net (code "31") (name "Net-(CVOUT2-Pad1)") (class "Default")
      (node (ref "CVOUT2") (pin "1") (pinfunction "1_1") (pintype "passive"))
      (node (ref "R27") (pin "2") (pinfunction "2_2") (pintype "passive"))
    )
    (net (code "32") (name "Net-(CVOUT3-Pad1)") (class "Default")
      (node (ref "CVOUT3") (pin "1") (pinfunction "1_1") (pintype "passive"))
      (node (ref "R32") (pin "2") (pinfunction "2_2") (pintype "passive"))
    )
    (net (code "33") (name "Net-(CVOUT4-Pad1)") (class "Default")
      (node (ref "CVOUT4") (pin "1") (pinfunction "1_1") (pintype "passive"))
      (node (ref "R38") (pin "2") (pinfunction "2_2") (pintype "passive"))
    )
    (net (code "34") (name "Net-(D1-Pad+)") (class "Default")
      (node (ref "D1") (pin "+") (pinfunction "+_+") (pintype "passive"))
      (node (ref "P4") (pin "10") (pinfunction "+12V_10") (pintype "bidirectional"))
      (node (ref "P4") (pin "9") (pinfunction "+12V_9") (pintype "bidirectional"))
    )
    (net (code "35") (name "Net-(D2-Pad-)") (class "Default")
      (node (ref "D2") (pin "-") (pinfunction "-_-") (pintype "passive"))
      (node (ref "P4") (pin "1") (pinfunction "-12V_1") (pintype "bidirectional"))
      (node (ref "P4") (pin "2") (pinfunction "-12V_2") (pintype "bidirectional"))
    )
    (net (code "36") (name "Net-(F1-P$2)") (class "Default")
      (node (ref "D1") (pin "-") (pinfunction "-_-") (pintype "passive"))
      (node (ref "F1") (pin "2") (pinfunction "P$2_2") (pintype "bidirectional"))
    )
    (net (code "37") (name "Net-(F2-P$2)") (class "Default")
      (node (ref "D2") (pin "+") (pinfunction "+_+") (pintype "passive"))
      (node (ref "F2") (pin "2") (pinfunction "P$2_2") (pintype "bidirectional"))
    )
    (net (code "38") (name "Net-(IC1A--IN)") (class "Default")
      (node (ref "IC1") (pin "2") (pinfunction "-IN_2") (pintype "input"))
      (node (ref "R18") (pin "2") (pinfunction "2_2") (pintype "passive"))
      (node (ref "R19") (pin "1") (pinfunction "1_1") (pintype "passive"))
    )
    (net (code "39") (name "Net-(IC1A-OUT)") (class "Default")
      (node (ref "IC1") (pin "1") (pinfunction "OUT_1") (pintype "output"))
      (node (ref "R19") (pin "2") (pinfunction "2_2") (pintype "passive"))
      (node (ref "R20") (pin "1") (pinfunction "1_1") (pintype "passive"))
    )
    (net (code "40") (name "Net-(IC1B--IN)") (class "Default")
      (node (ref "IC1") (pin "6") (pinfunction "-IN_6") (pintype "input"))
      (node (ref "R20") (pin "2") (pinfunction "2_2") (pintype "passive"))
      (node (ref "R21") (pin "1") (pinfunction "1_1") (pintype "passive"))
    )
    (net (code "41") (name "Net-(IC1B-OUT)") (class "Default")
      (node (ref "IC1") (pin "7") (pinfunction "OUT_7") (pintype "output"))
      (node (ref "R21") (pin "2") (pinfunction "2_2") (pintype "passive"))
      (node (ref "R22") (pin "1") (pinfunction "1_1") (pintype "passive"))
    )
    (net (code "42") (name "Net-(IC1C--IN)") (class "Default")
      (node (ref "IC1") (pin "9") (pinfunction "-IN_9") (pintype "input"))
      (node (ref "R23") (pin "2") (pinfunction "2_2") (pintype "passive"))
      (node (ref "R24") (pin "1") (pinfunction "1_1") (pintype "passive"))
    )
    (net (code "43") (name "Net-(IC1C-OUT)") (class "Default")
      (node (ref "IC1") (pin "8") (pinfunction "OUT_8") (pintype "output"))
      (node (ref "R24") (pin "2") (pinfunction "2_2") (pintype "passive"))
      (node (ref "R25") (pin "1") (pinfunction "1_1") (pintype "passive"))
    )
    (net (code "44") (name "Net-(IC1D--IN)") (class "Default")
      (node (ref "IC1") (pin "13") (pinfunction "-IN_13") (pintype "input"))
      (node (ref "R25") (pin "2") (pinfunction "2_2") (pintype "passive"))
      (node (ref "R26") (pin "1") (pinfunction "1_1") (pintype "passive"))
    )
    (net (code "45") (name "Net-(IC1D-OUT)") (class "Default")
      (node (ref "IC1") (pin "14") (pinfunction "OUT_14") (pintype "output"))
      (node (ref "R26") (pin "2") (pinfunction "2_2") (pintype "passive"))
      (node (ref "R27") (pin "1") (pinfunction "1_1") (pintype "passive"))
    )
    (net (code "46") (name "Net-(IC2A-P$2)") (class "Default")
      (node (ref "IC2") (pin "2") (pinfunction "P$2_2") (pintype "bidirectional"))
      (node (ref "R4") (pin "1") (pinfunction "1_1") (pintype "passive"))
      (node (ref "R8") (pin "2") (pinfunction "2_2") (pintype "passive"))
    )
    (net (code "47") (name "Net-(IC2A-P$3)") (class "Default")
      (node (ref "IC2") (pin "1") (pinfunction "P$3_1") (pintype "bidirectional"))
      (node (ref "R14") (pin "2") (pinfunction "2_2") (pintype "passive"))
      (node (ref "R8") (pin "1") (pinfunction "1_1") (pintype "passive"))
    )
    (net (code "48") (name "Net-(IC2B-P$2)") (class "Default")
      (node (ref "IC2") (pin "6") (pinfunction "P$2_6") (pintype "bidirectional"))
      (node (ref "R5") (pin "1") (pinfunction "1_1") (pintype "passive"))
      (node (ref "R9") (pin "2") (pinfunction "2_2") (pintype "passive"))
    )
    (net (code "49") (name "Net-(IC2B-P$3)") (class "Default")
      (node (ref "IC2") (pin "7") (pinfunction "P$3_7") (pintype "bidirectional"))
      (node (ref "R15") (pin "2") (pinfunction "2_2") (pintype "passive"))
      (node (ref "R9") (pin "1") (pinfunction "1_1") (pintype "passive"))
    )
    (net (code "50") (name "Net-(IC3A-P$2)") (class "Default")
      (node (ref "C7") (pin "2") (pinfunction "2_2") (pintype "passive"))
      (node (ref "IC3") (pin "2") (pinfunction "P$2_2") (pintype "bidirectional"))
      (node (ref "R10") (pin "1") (pinfunction "1_1") (pintype "passive"))
      (node (ref "R6") (pin "2") (pinfunction "2_2") (pintype "passive"))
    )
    (net (code "51") (name "Net-(IC3A-P$3)") (class "Default")
      (node (ref "C7") (pin "1") (pinfunction "1_1") (pintype "passive"))
      (node (ref "IC3") (pin "1") (pinfunction "P$3_1") (pintype "bidirectional"))
      (node (ref "R10") (pin "2") (pinfunction "2_2") (pintype "passive"))
      (node (ref "R12") (pin "1") (pinfunction "1_1") (pintype "passive"))
    )
    (net (code "52") (name "Net-(IC3B-P$2)") (class "Default")
      (node (ref "C8") (pin "2") (pinfunction "2_2") (pintype "passive"))
      (node (ref "IC3") (pin "6") (pinfunction "P$2_6") (pintype "bidirectional"))
      (node (ref "R11") (pin "1") (pinfunction "1_1") (pintype "passive"))
      (node (ref "R7") (pin "2") (pinfunction "2_2") (pintype "passive"))
    )
    (net (code "53") (name "Net-(IC3B-P$3)") (class "Default")
      (node (ref "C8") (pin "1") (pinfunction "1_1") (pintype "passive"))
      (node (ref "IC3") (pin "7") (pinfunction "P$3_7") (pintype "bidirectional"))
      (node (ref "R11") (pin "2") (pinfunction "2_2") (pintype "passive"))
      (node (ref "R13") (pin "1") (pinfunction "1_1") (pintype "passive"))
    )
    (net (code "54") (name "Net-(IC4-VMID)") (class "Default")
      (node (ref "C11") (pin "1") (pinfunction "1_1") (pintype "passive"))
      (node (ref "C14") (pin "1") (pinfunction "1_1") (pintype "passive"))
      (node (ref "IC4") (pin "16") (pinfunction "VMID_16") (pintype "bidirectional"))
    )
    (net (code "55") (name "Net-(IC4-XTI{slash}MCLK)") (class "Default")
      (node (ref "C4") (pin "2") (pinfunction "2_2") (pintype "passive"))
      (node (ref "IC4") (pin "25") (pinfunction "XTI/MCLK_25") (pintype "bidirectional"))
      (node (ref "Q1") (pin "1") (pinfunction "1_1") (pintype "passive"))
    )
    (net (code "56") (name "Net-(IC4-XTO)") (class "Default")
      (node (ref "C5") (pin "2") (pinfunction "2_2") (pintype "passive"))
      (node (ref "IC4") (pin "26") (pinfunction "XTO_26") (pintype "bidirectional"))
      (node (ref "Q1") (pin "2") (pinfunction "2_2") (pintype "passive"))
    )
    (net (code "57") (name "Net-(IC5A--IN)") (class "Default")
      (node (ref "IC5") (pin "2") (pinfunction "-IN_2") (pintype "input"))
      (node (ref "R28") (pin "2") (pinfunction "2_2") (pintype "passive"))
      (node (ref "R29") (pin "1") (pinfunction "1_1") (pintype "passive"))
    )
    (net (code "58") (name "Net-(IC5A-OUT)") (class "Default")
      (node (ref "IC5") (pin "1") (pinfunction "OUT_1") (pintype "output"))
      (node (ref "R29") (pin "2") (pinfunction "2_2") (pintype "passive"))
      (node (ref "R30") (pin "1") (pinfunction "1_1") (pintype "passive"))
    )
    (net (code "59") (name "Net-(IC5B--IN)") (class "Default")
      (node (ref "IC5") (pin "6") (pinfunction "-IN_6") (pintype "input"))
      (node (ref "R30") (pin "2") (pinfunction "2_2") (pintype "passive"))
      (node (ref "R31") (pin "1") (pinfunction "1_1") (pintype "passive"))
    )
    (net (code "60") (name "Net-(IC5B-OUT)") (class "Default")
      (node (ref "IC5") (pin "7") (pinfunction "OUT_7") (pintype "output"))
      (node (ref "R31") (pin "2") (pinfunction "2_2") (pintype "passive"))
      (node (ref "R32") (pin "1") (pinfunction "1_1") (pintype "passive"))
    )
    (net (code "61") (name "Net-(IC5C--IN)") (class "Default")
      (node (ref "IC5") (pin "9") (pinfunction "-IN_9") (pintype "input"))
      (node (ref "R34") (pin "2") (pinfunction "2_2") (pintype "passive"))
      (node (ref "R35") (pin "1") (pinfunction "1_1") (pintype "passive"))
    )
    (net (code "62") (name "Net-(IC5C-OUT)") (class "Default")
      (node (ref "IC5") (pin "8") (pinfunction "OUT_8") (pintype "output"))
      (node (ref "R35") (pin "2") (pinfunction "2_2") (pintype "passive"))
      (node (ref "R36") (pin "1") (pinfunction "1_1") (pintype "passive"))
    )
    (net (code "63") (name "Net-(IC5D--IN)") (class "Default")
      (node (ref "IC5") (pin "13") (pinfunction "-IN_13") (pintype "input"))
      (node (ref "R36") (pin "2") (pinfunction "2_2") (pintype "passive"))
      (node (ref "R37") (pin "1") (pinfunction "1_1") (pintype "passive"))
    )
    (net (code "64") (name "Net-(IC5D-OUT)") (class "Default")
      (node (ref "IC5") (pin "14") (pinfunction "OUT_14") (pintype "output"))
      (node (ref "R37") (pin "2") (pinfunction "2_2") (pintype "passive"))
      (node (ref "R38") (pin "1") (pinfunction "1_1") (pintype "passive"))
    )
    (net (code "65") (name "Net-(IC10A-P$2)") (class "Default")
      (node (ref "C49") (pin "1") (pinfunction "1_1") (pintype "passive"))
      (node (ref "CVIN(100K)0") (pin "1") (pinfunction "1_1") (pintype "passive"))
      (node (ref "IC10") (pin "2") (pinfunction "P$2_2") (pintype "bidirectional"))
      (node (ref "R3") (pin "1") (pinfunction "1_1") (pintype "passive"))
      (node (ref "R46") (pin "1") (pinfunction "1_1") (pintype "passive"))
    )
    (net (code "66") (name "Net-(IC10B-P$2)") (class "Default")
      (node (ref "C50") (pin "1") (pinfunction "1_1") (pintype "passive"))
      (node (ref "CVIN(100K)1") (pin "1") (pinfunction "1_1") (pintype "passive"))
      (node (ref "IC10") (pin "6") (pinfunction "P$2_6") (pintype "bidirectional"))
      (node (ref "R39") (pin "1") (pinfunction "1_1") (pintype "passive"))
      (node (ref "R47") (pin "1") (pinfunction "1_1") (pintype "passive"))
    )
    (net (code "67") (name "Net-(IC10C-P$2)") (class "Default")
      (node (ref "C53") (pin "1") (pinfunction "1_1") (pintype "passive"))
      (node (ref "CVIN(100K)2") (pin "1") (pinfunction "1_1") (pintype "passive"))
      (node (ref "IC10") (pin "9") (pinfunction "P$2_9") (pintype "bidirectional"))
      (node (ref "R40") (pin "1") (pinfunction "1_1") (pintype "passive"))
      (node (ref "R58") (pin "1") (pinfunction "1_1") (pintype "passive"))
    )
    (net (code "68") (name "Net-(IC10D-P$2)") (class "Default")
      (node (ref "C54") (pin "1") (pinfunction "1_1") (pintype "passive"))
      (node (ref "CVIN(100K)3") (pin "1") (pinfunction "1_1") (pintype "passive"))
      (node (ref "IC10") (pin "13") (pinfunction "P$2_13") (pintype "bidirectional"))
      (node (ref "R41") (pin "1") (pinfunction "1_1") (pintype "passive"))
      (node (ref "R59") (pin "1") (pinfunction "1_1") (pintype "passive"))
    )
    (net (code "69") (name "Net-(J_LIN-Pad1)") (class "Default")
      (node (ref "J_LIN") (pin "1") (pinfunction "1_1") (pintype "passive"))
      (node (ref "R5") (pin "2") (pinfunction "2_2") (pintype "passive"))
    )
    (net (code "70") (name "Net-(J_LOUT-Pad1)") (class "Default")
      (node (ref "J_LOUT") (pin "1") (pinfunction "1_1") (pintype "passive"))
      (node (ref "R13") (pin "2") (pinfunction "2_2") (pintype "passive"))
    )
    (net (code "71") (name "Net-(J_RIN-Pad1)") (class "Default")
      (node (ref "J_RIN") (pin "1") (pinfunction "1_1") (pintype "passive"))
      (node (ref "R4") (pin "2") (pinfunction "2_2") (pintype "passive"))
    )
    (net (code "72") (name "Net-(J_ROUT-Pad1)") (class "Default")
      (node (ref "J_ROUT") (pin "1") (pinfunction "1_1") (pintype "passive"))
      (node (ref "R12") (pin "2") (pinfunction "2_2") (pintype "passive"))
    )
    (net (code "73") (name "Net-(MS2-A2{slash}I34)") (class "Default")
      (node (ref "MS2") (pin "7") (pinfunction "A2/I34_7") (pintype "bidirectional"))
      (node (ref "P1") (pin "1") (pinfunction "1_1") (pintype "passive"))
    )
    (net (code "74") (name "Net-(MS2-A3{slash}I39)") (class "Default")
      (node (ref "MS2") (pin "8") (pinfunction "A3/I39_8") (pintype "bidirectional"))
      (node (ref "P2") (pin "1") (pinfunction "1_1") (pintype "passive"))
    )
    (net (code "75") (name "Net-(MS2-A4{slash}I36)") (class "Default")
      (node (ref "MS2") (pin "9") (pinfunction "A4/I36_9") (pintype "bidirectional"))
      (node (ref "P3") (pin "1") (pinfunction "1_1") (pintype "passive"))
    )
    (net (code "76") (name "Net-(MS2-IO13)") (class "Default")
      (node (ref "MS2") (pin "25") (pinfunction "IO13_25") (pintype "bidirectional"))
      (node (ref "P9") (pin "1") (pinfunction "1_1") (pintype "passive"))
    )
    (net (code "77") (name "Net-(MS2-RX{slash}IO16)") (class "Default")
      (node (ref "MS2") (pin "14") (pinfunction "RX/IO16_14") (pintype "bidirectional"))
      (node (ref "P5") (pin "1") (pinfunction "1_1") (pintype "passive"))
    )
    (net (code "78") (name "Net-(MS2-SCL)") (class "Default")
      (node (ref "MS2") (pin "18") (pinfunction "SCL_18") (pintype "bidirectional"))
      (node (ref "P8") (pin "1") (pinfunction "1_1") (pintype "passive"))
    )
    (net (code "79") (name "Net-(MS2-SDA)") (class "Default")
      (node (ref "MS2") (pin "17") (pinfunction "SDA_17") (pintype "bidirectional"))
      (node (ref "P7") (pin "1") (pinfunction "1_1") (pintype "passive"))
    )
    (net (code "80") (name "Net-(MS2-TX{slash}IO17)") (class "Default")
      (node (ref "MS2") (pin "15") (pinfunction "TX/IO17_15") (pintype "bidirectional"))
      (node (ref "P6") (pin "1") (pinfunction "1_1") (pintype "passive"))
    )
    (net (code "81") (name "Net-(U$1-VOUTA)") (class "Default")
      (node (ref "R18") (pin "1") (pinfunction "1_1") (pintype "passive"))
      (node (ref "U$1") (pin "8") (pinfunction "VOUTA_8") (pintype "output"))
    )
    (net (code "82") (name "Net-(U$1-VOUTB)") (class "Default")
      (node (ref "R23") (pin "1") (pinfunction "1_1") (pintype "passive"))
      (node (ref "U$1") (pin "6") (pinfunction "VOUTB_6") (pintype "output"))
    )
    (net (code "83") (name "Net-(U$2-VOUTA)") (class "Default")
      (node (ref "R28") (pin "1") (pinfunction "1_1") (pintype "passive"))
      (node (ref "U$2") (pin "8") (pinfunction "VOUTA_8") (pintype "output"))
    )
    (net (code "84") (name "Net-(U$2-VOUTB)") (class "Default")
      (node (ref "R34") (pin "1") (pinfunction "1_1") (pintype "passive"))
      (node (ref "U$2") (pin "6") (pinfunction "VOUTB_6") (pintype "output"))
    )
    (net (code "85") (name "RIN") (class "Default")
      (node (ref "C12") (pin "1") (pinfunction "1_1") (pintype "passive"))
      (node (ref "IC4") (pin "19") (pinfunction "RLINEIN_19") (pintype "bidirectional"))
    )
    (net (code "86") (name "ROUT") (class "Default")
      (node (ref "C2") (pin "2") (pinfunction "2_2") (pintype "passive"))
      (node (ref "IC4") (pin "13") (pinfunction "ROUT_13") (pintype "bidirectional"))
    )
    (net (code "87") (name "SPI_CLK") (class "Default")
      (node (ref "MS2") (pin "11") (pinfunction "SCK_11") (pintype "bidirectional"))
      (node (ref "U$1") (pin "3") (pinfunction "SCK_3") (pintype "input"))
      (node (ref "U$2") (pin "3") (pinfunction "SCK_3") (pintype "input"))
      (node (ref "U2") (pin "11") (pinfunction "CLK_11") (pintype "input"))
    )
    (net (code "88") (name "SPI_MISO") (class "Default")
      (node (ref "MS2") (pin "13") (pinfunction "MISO_13") (pintype "bidirectional"))
      (node (ref "U2") (pin "10") (pinfunction "DOUT_10") (pintype "output"))
    )
    (net (code "89") (name "SPI_MOSI") (class "Default")
      (node (ref "MS2") (pin "12") (pinfunction "MOSI_12") (pintype "bidirectional"))
      (node (ref "U$1") (pin "4") (pinfunction "SDI_4") (pintype "input"))
      (node (ref "U$2") (pin "4") (pinfunction "SDI_4") (pintype "input"))
      (node (ref "U2") (pin "9") (pinfunction "DIN_9") (pintype "input"))
    )
    (net (code "90") (name "unconnected-(IC4-CLKOUT-Pad2)") (class "Default")
      (node (ref "IC4") (pin "2") (pinfunction "CLKOUT_2") (pintype "bidirectional"))
    )
    (net (code "91") (name "unconnected-(IC4-LHPOUT-Pad9)") (class "Default")
      (node (ref "IC4") (pin "9") (pinfunction "LHPOUT_9") (pintype "bidirectional"))
    )
    (net (code "92") (name "unconnected-(IC4-MICBIAS-Pad17)") (class "Default")
      (node (ref "IC4") (pin "17") (pinfunction "MICBIAS_17") (pintype "bidirectional"))
    )
    (net (code "93") (name "unconnected-(IC4-MICIN-Pad18)") (class "Default")
      (node (ref "IC4") (pin "18") (pinfunction "MICIN_18") (pintype "bidirectional"))
    )
    (net (code "94") (name "unconnected-(IC4-RHPOUT-Pad10)") (class "Default")
      (node (ref "IC4") (pin "10") (pinfunction "RHPOUT_10") (pintype "bidirectional"))
    )
    (net (code "95") (name "unconnected-(MS2-EN-Pad27)") (class "Default")
      (node (ref "MS2") (pin "27") (pinfunction "EN_27") (pintype "passive"))
    )
    (net (code "96") (name "unconnected-(MS2-NC-Pad3)") (class "Default")
      (node (ref "MS2") (pin "3") (pinfunction "NC_3") (pintype "passive"))
    )
    (net (code "97") (name "unconnected-(MS2-~{RESET}-Pad1)") (class "Default")
      (node (ref "MS2") (pin "1") (pinfunction "~{RESET}_1") (pintype "input"))
    )
    (net (code "98") (name "unconnected-(U2-NC-Pad6)") (class "Default")
      (node (ref "U2") (pin "6") (pinfunction "NC_6") (pintype "no_connect"))
    )
    (net (code "99") (name "unconnected-(U2-NC_2-Pad5)") (class "Default")
      (node (ref "U2") (pin "5") (pinfunction "NC_2_5") (pintype "no_connect"))
    )
  )
)
